# Op-Amp_Stages.net
KiCad netlist of a schematic drawn in Altium Designer
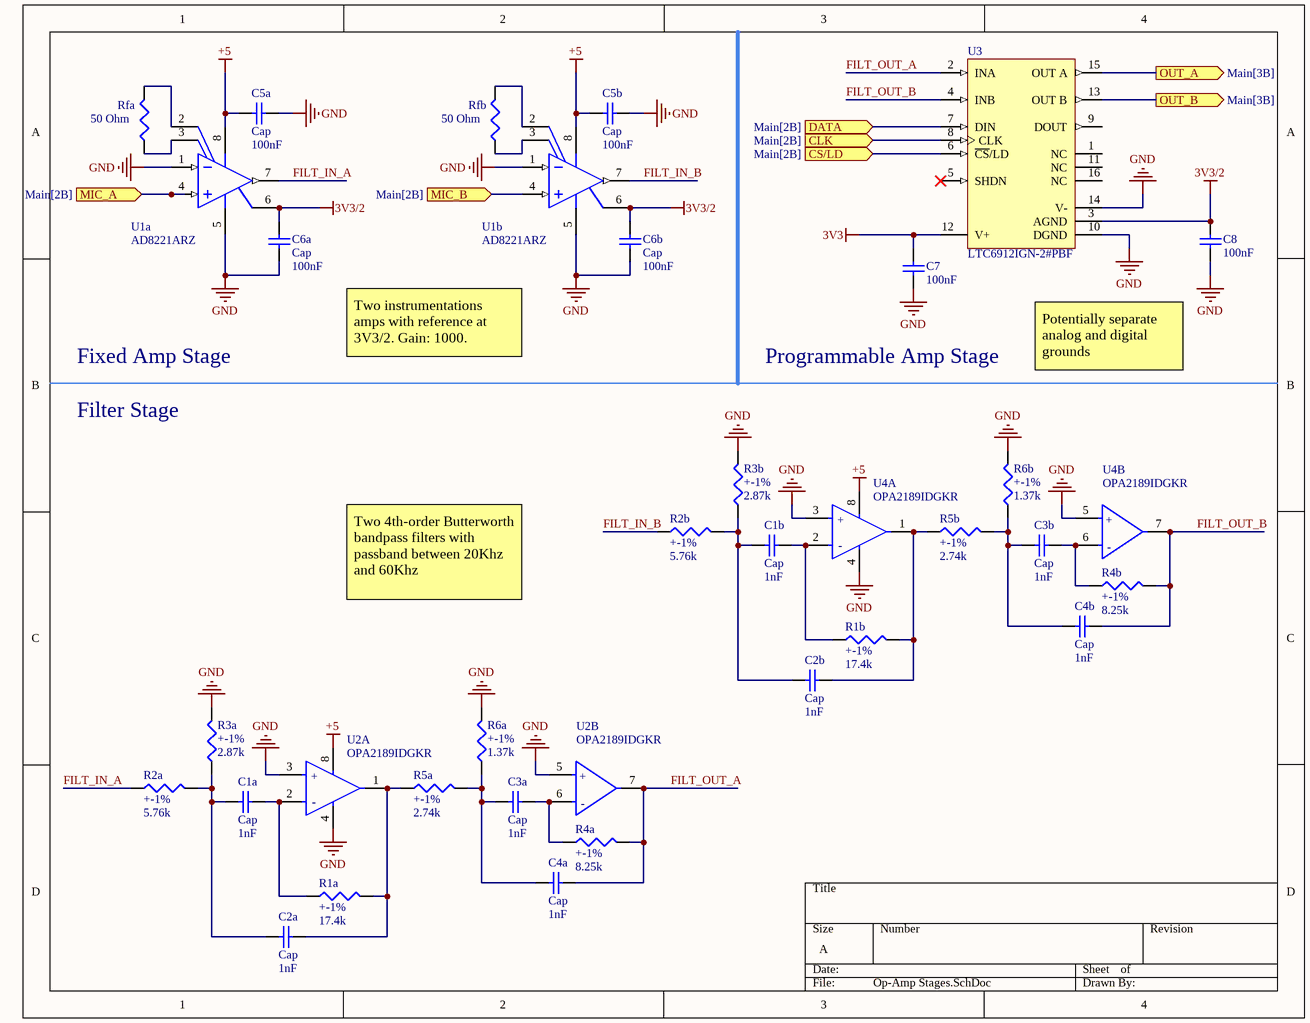
[diagram p0: Op-Amp Stages.SchDoc]

(export (version "E")
  (design (tool "Eeschema 10.0.6"))
  (components
    (comp (ref "C1a")
      (value "Cap")
      (footprint "RAD-0.3")
      (description "Capacitor")
      (fields (field (name "ALTIUM_VALUE") "1nF") (field (name "PUBLISHER") "Altium Limited"))
      (libsource (lib "Miscellaneous Devices") (part "Cap"))
    )
    (comp (ref "C1b")
      (value "Cap")
      (footprint "RAD-0.3")
      (description "Capacitor")
      (fields (field (name "ALTIUM_VALUE") "1nF") (field (name "PUBLISHER") "Altium Limited"))
      (libsource (lib "Miscellaneous Devices") (part "Cap"))
    )
    (comp (ref "C2a")
      (value "Cap")
      (footprint "RAD-0.3")
      (description "Capacitor")
      (fields (field (name "ALTIUM_VALUE") "1nF") (field (name "PUBLISHER") "Altium Limited"))
      (libsource (lib "Miscellaneous Devices") (part "Cap"))
    )
    (comp (ref "C2b")
      (value "Cap")
      (footprint "RAD-0.3")
      (description "Capacitor")
      (fields (field (name "ALTIUM_VALUE") "1nF") (field (name "PUBLISHER") "Altium Limited"))
      (libsource (lib "Miscellaneous Devices") (part "Cap"))
    )
    (comp (ref "C3a")
      (value "Cap")
      (footprint "RAD-0.3")
      (description "Capacitor")
      (fields (field (name "ALTIUM_VALUE") "1nF") (field (name "PUBLISHER") "Altium Limited"))
      (libsource (lib "Miscellaneous Devices") (part "Cap"))
    )
    (comp (ref "C3b")
      (value "Cap")
      (footprint "RAD-0.3")
      (description "Capacitor")
      (fields (field (name "ALTIUM_VALUE") "1nF") (field (name "PUBLISHER") "Altium Limited"))
      (libsource (lib "Miscellaneous Devices") (part "Cap"))
    )
    (comp (ref "C4a")
      (value "Cap")
      (footprint "RAD-0.3")
      (description "Capacitor")
      (fields (field (name "ALTIUM_VALUE") "1nF") (field (name "PUBLISHER") "Altium Limited"))
      (libsource (lib "Miscellaneous Devices") (part "Cap"))
    )
    (comp (ref "C4b")
      (value "Cap")
      (footprint "RAD-0.3")
      (description "Capacitor")
      (fields (field (name "ALTIUM_VALUE") "1nF") (field (name "PUBLISHER") "Altium Limited"))
      (libsource (lib "Miscellaneous Devices") (part "Cap"))
    )
    (comp (ref "C5a")
      (value "Cap")
      (footprint "RAD-0.3")
      (description "Capacitor")
      (fields (field (name "ALTIUM_VALUE") "100nF") (field (name "PUBLISHER") "Altium Limited"))
      (libsource (lib "Miscellaneous Devices") (part "Cap"))
    )
    (comp (ref "C5b")
      (value "Cap")
      (footprint "RAD-0.3")
      (description "Capacitor")
      (fields (field (name "ALTIUM_VALUE") "100nF") (field (name "PUBLISHER") "Altium Limited"))
      (libsource (lib "Miscellaneous Devices") (part "Cap"))
    )
    (comp (ref "C6a")
      (value "Cap")
      (footprint "RAD-0.3")
      (description "Capacitor")
      (fields (field (name "ALTIUM_VALUE") "100nF") (field (name "PUBLISHER") "Altium Limited"))
      (libsource (lib "Miscellaneous Devices") (part "Cap"))
    )
    (comp (ref "C6b")
      (value "Cap")
      (footprint "RAD-0.3")
      (description "Capacitor")
      (fields (field (name "ALTIUM_VALUE") "100nF") (field (name "PUBLISHER") "Altium Limited"))
      (libsource (lib "Miscellaneous Devices") (part "Cap"))
    )
    (comp (ref "C7")
      (value "100nF")
      (footprint "RAD-0.3")
      (description "Capacitor")
      (fields (field (name "PUBLISHER") "Altium Limited"))
      (libsource (lib "Miscellaneous Devices") (part "Cap"))
    )
    (comp (ref "C8")
      (value "100nF")
      (footprint "RAD-0.3")
      (description "Capacitor")
      (fields (field (name "PUBLISHER") "Altium Limited"))
      (libsource (lib "Miscellaneous Devices") (part "Cap"))
    )
    (comp (ref "R1a")
      (value "+-1%")
      (footprint "J1-0603")
      (description "Resistor")
      (fields (field (name "ALTIUM_VALUE") "17.4k") (field (name "PUBLISHER") "Altium Limited"))
      (libsource (lib "Miscellaneous Devices") (part "Res3"))
    )
    (comp (ref "R1b")
      (value "+-1%")
      (footprint "J1-0603")
      (description "Resistor")
      (fields (field (name "ALTIUM_VALUE") "17.4k") (field (name "PUBLISHER") "Altium Limited"))
      (libsource (lib "Miscellaneous Devices") (part "Res3"))
    )
    (comp (ref "R2a")
      (value "+-1%")
      (footprint "J1-0603")
      (description "Resistor")
      (fields (field (name "ALTIUM_VALUE") "5.76k") (field (name "PUBLISHER") "Altium Limited"))
      (libsource (lib "Miscellaneous Devices") (part "Res3"))
    )
    (comp (ref "R2b")
      (value "+-1%")
      (footprint "J1-0603")
      (description "Resistor")
      (fields (field (name "ALTIUM_VALUE") "5.76k") (field (name "PUBLISHER") "Altium Limited"))
      (libsource (lib "Miscellaneous Devices") (part "Res3"))
    )
    (comp (ref "R3a")
      (value "+-1%")
      (footprint "J1-0603")
      (description "Resistor")
      (fields (field (name "ALTIUM_VALUE") "2.87k") (field (name "PUBLISHER") "Altium Limited"))
      (libsource (lib "Miscellaneous Devices") (part "Res3"))
    )
    (comp (ref "R3b")
      (value "+-1%")
      (footprint "J1-0603")
      (description "Resistor")
      (fields (field (name "ALTIUM_VALUE") "2.87k") (field (name "PUBLISHER") "Altium Limited"))
      (libsource (lib "Miscellaneous Devices") (part "Res3"))
    )
    (comp (ref "R4a")
      (value "+-1%")
      (footprint "J1-0603")
      (description "Resistor")
      (fields (field (name "ALTIUM_VALUE") "8.25k") (field (name "PUBLISHER") "Altium Limited"))
      (libsource (lib "Miscellaneous Devices") (part "Res3"))
    )
    (comp (ref "R4b")
      (value "+-1%")
      (footprint "J1-0603")
      (description "Resistor")
      (fields (field (name "ALTIUM_VALUE") "8.25k") (field (name "PUBLISHER") "Altium Limited"))
      (libsource (lib "Miscellaneous Devices") (part "Res3"))
    )
    (comp (ref "R5a")
      (value "+-1%")
      (footprint "J1-0603")
      (description "Resistor")
      (fields (field (name "ALTIUM_VALUE") "2.74k") (field (name "PUBLISHER") "Altium Limited"))
      (libsource (lib "Miscellaneous Devices") (part "Res3"))
    )
    (comp (ref "R5b")
      (value "+-1%")
      (footprint "J1-0603")
      (description "Resistor")
      (fields (field (name "ALTIUM_VALUE") "2.74k") (field (name "PUBLISHER") "Altium Limited"))
      (libsource (lib "Miscellaneous Devices") (part "Res3"))
    )
    (comp (ref "R6a")
      (value "+-1%")
      (footprint "J1-0603")
      (description "Resistor")
      (fields (field (name "ALTIUM_VALUE") "1.37k") (field (name "PUBLISHER") "Altium Limited"))
      (libsource (lib "Miscellaneous Devices") (part "Res3"))
    )
    (comp (ref "R6b")
      (value "+-1%")
      (footprint "J1-0603")
      (description "Resistor")
      (fields (field (name "ALTIUM_VALUE") "1.37k") (field (name "PUBLISHER") "Altium Limited"))
      (libsource (lib "Miscellaneous Devices") (part "Res3"))
    )
    (comp (ref "Rfa")
      (value "50 Ohm")
      (footprint "J1-0603")
      (description "Resistor")
      (fields (field (name "PUBLISHER") "Altium Limited"))
      (libsource (lib "Miscellaneous Devices") (part "Res3"))
    )
    (comp (ref "Rfb")
      (value "50 Ohm")
      (footprint "J1-0603")
      (description "Resistor")
      (fields (field (name "PUBLISHER") "Altium Limited"))
      (libsource (lib "Miscellaneous Devices") (part "Res3"))
    )
    (comp (ref "U1a")
      (value "AD8221ARZ")
      (footprint "ADI-R-8_M")
      (description "Precision Instrumentation Amplifier, 2 V/us, -40 to 125 degC, 8-Pin SOIC (R-8), RoHS, Tube")
      (fields (field (name "MANUFACTURER") "Analog Devices"))
      (libsource (lib "Altium Content Vault") (part "ADI-AD8221-8"))
    )
    (comp (ref "U1b")
      (value "AD8221ARZ")
      (footprint "ADI-R-8_M")
      (description "Precision Instrumentation Amplifier, 2 V/us, -40 to 125 degC, 8-Pin SOIC (R-8), RoHS, Tube")
      (fields (field (name "MANUFACTURER") "Analog Devices"))
      (libsource (lib "Altium Content Vault") (part "ADI-AD8221-8"))
    )
    (comp (ref "U2")
      (value "OPA2189IDGKR")
      (footprint "FP-DGK0008A-IPC_B")
      (description "DUAL, 14MHZ, MUX-FRIENDLY, LOW-N")
      (libsource (lib "Altium Content Vault") (part "499df5fc91ff7ad023bcaf249d8becd"))
    )
    (comp (ref "U3")
      (value "LTC6912IGN-2#PBF")
      (footprint "LT-GN-16_L")
      (fields
        (field (name "MANUFACTURER") "Linear Technology")
        (field (name "LINEAR TECHNOLOGY PART NUMBER") "LTC6912-2")
      )
      (libsource (lib "Altium Content Vault") (part "LT-LTC6912-2-GN-16"))
    )
    (comp (ref "U4")
      (value "OPA2189IDGKR")
      (footprint "FP-DGK0008A-IPC_B")
      (description "DUAL, 14MHZ, MUX-FRIENDLY, LOW-N")
      (libsource (lib "Altium Content Vault") (part "499df5fc91ff7ad023bcaf249d8becd"))
    )
  )
  (nets
    (net (code "1") (name "+5") (class "Default")
      (node (ref "C5a") (pin "1") (pinfunction "1_1") (pintype "passive"))
      (node (ref "C5b") (pin "1") (pinfunction "1_1") (pintype "passive"))
      (node (ref "U1a") (pin "8") (pinfunction "VS+_8") (pintype "power_in"))
      (node (ref "U1b") (pin "8") (pinfunction "VS+_8") (pintype "power_in"))
      (node (ref "U2") (pin "8") (pinfunction "V+_8") (pintype "power_in"))
      (node (ref "U4") (pin "8") (pinfunction "V+_8") (pintype "power_in"))
    )
    (net (code "2") (name "/CLK") (class "Default")
      (node (ref "U3") (pin "8") (pinfunction "CLK_8") (pintype "input"))
    )
    (net (code "3") (name "/CS{slash}LD") (class "Default")
      (node (ref "U3") (pin "6") (pinfunction "~{CS}/LD_6") (pintype "input"))
    )
    (net (code "4") (name "/DATA") (class "Default")
      (node (ref "U3") (pin "7") (pinfunction "DIN_7") (pintype "input"))
    )
    (net (code "5") (name "/FILT_IN_A") (class "Default")
      (node (ref "R2a") (pin "1") (pinfunction "1_1") (pintype "passive"))
      (node (ref "U1a") (pin "7") (pinfunction "VOUT_7") (pintype "output"))
    )
    (net (code "6") (name "/FILT_IN_B") (class "Default")
      (node (ref "R2b") (pin "1") (pinfunction "1_1") (pintype "passive"))
      (node (ref "U1b") (pin "7") (pinfunction "VOUT_7") (pintype "output"))
    )
    (net (code "7") (name "/FILT_OUT_A") (class "Default")
      (node (ref "C4a") (pin "2") (pinfunction "2_2") (pintype "passive"))
      (node (ref "R4a") (pin "2") (pinfunction "2_2") (pintype "passive"))
      (node (ref "U2") (pin "7") (pinfunction "OUT_B_7") (pintype "passive"))
      (node (ref "U3") (pin "2") (pinfunction "INA_2") (pintype "input"))
    )
    (net (code "8") (name "/FILT_OUT_B") (class "Default")
      (node (ref "C4b") (pin "2") (pinfunction "2_2") (pintype "passive"))
      (node (ref "R4b") (pin "2") (pinfunction "2_2") (pintype "passive"))
      (node (ref "U3") (pin "4") (pinfunction "INB_4") (pintype "input"))
      (node (ref "U4") (pin "7") (pinfunction "OUT_B_7") (pintype "passive"))
    )
    (net (code "9") (name "/MIC_A") (class "Default")
      (node (ref "U1a") (pin "4") (pinfunction "IN+_4") (pintype "input"))
    )
    (net (code "10") (name "/MIC_B") (class "Default")
      (node (ref "U1b") (pin "4") (pinfunction "IN+_4") (pintype "input"))
    )
    (net (code "11") (name "/OUT_A") (class "Default")
      (node (ref "U3") (pin "15") (pinfunction "OUT_A_15") (pintype "output"))
    )
    (net (code "12") (name "/OUT_B") (class "Default")
      (node (ref "U3") (pin "13") (pinfunction "OUT_B_13") (pintype "output"))
    )
    (net (code "13") (name "3V3") (class "Default")
      (node (ref "C7") (pin "2") (pinfunction "2_2") (pintype "passive"))
      (node (ref "U3") (pin "12") (pinfunction "V+_12") (pintype "power_in"))
    )
    (net (code "14") (name "3V3{slash}2") (class "Default")
      (node (ref "C6a") (pin "2") (pinfunction "2_2") (pintype "passive"))
      (node (ref "C6b") (pin "2") (pinfunction "2_2") (pintype "passive"))
      (node (ref "C8") (pin "2") (pinfunction "2_2") (pintype "passive"))
      (node (ref "U1a") (pin "6") (pinfunction "REF_6") (pintype "passive"))
      (node (ref "U1b") (pin "6") (pinfunction "REF_6") (pintype "passive"))
      (node (ref "U3") (pin "3") (pinfunction "AGND_3") (pintype "power_in"))
    )
    (net (code "15") (name "GND") (class "Default")
      (node (ref "C5a") (pin "2") (pinfunction "2_2") (pintype "passive"))
      (node (ref "C5b") (pin "2") (pinfunction "2_2") (pintype "passive"))
      (node (ref "C6a") (pin "1") (pinfunction "1_1") (pintype "passive"))
      (node (ref "C6b") (pin "1") (pinfunction "1_1") (pintype "passive"))
      (node (ref "C7") (pin "1") (pinfunction "1_1") (pintype "passive"))
      (node (ref "C8") (pin "1") (pinfunction "1_1") (pintype "passive"))
      (node (ref "R3a") (pin "2") (pinfunction "2_2") (pintype "passive"))
      (node (ref "R3b") (pin "2") (pinfunction "2_2") (pintype "passive"))
      (node (ref "R6a") (pin "2") (pinfunction "2_2") (pintype "passive"))
      (node (ref "R6b") (pin "2") (pinfunction "2_2") (pintype "passive"))
      (node (ref "U1a") (pin "1") (pinfunction "IN-_1") (pintype "input"))
      (node (ref "U1a") (pin "5") (pinfunction "VS-_5") (pintype "power_in"))
      (node (ref "U1b") (pin "1") (pinfunction "IN-_1") (pintype "input"))
      (node (ref "U1b") (pin "5") (pinfunction "VS-_5") (pintype "power_in"))
      (node (ref "U2") (pin "3") (pinfunction "+IN_A_3") (pintype "tri_state"))
      (node (ref "U2") (pin "4") (pinfunction "V-_4") (pintype "power_in"))
      (node (ref "U2") (pin "5") (pinfunction "+IN_B_5") (pintype "tri_state"))
      (node (ref "U3") (pin "10") (pinfunction "DGND_10") (pintype "power_in"))
      (node (ref "U3") (pin "14") (pinfunction "V-_14") (pintype "power_in"))
      (node (ref "U4") (pin "3") (pinfunction "+IN_A_3") (pintype "tri_state"))
      (node (ref "U4") (pin "4") (pinfunction "V-_4") (pintype "power_in"))
      (node (ref "U4") (pin "5") (pinfunction "+IN_B_5") (pintype "tri_state"))
    )
    (net (code "16") (name "Net-(C1a-Pad1)") (class "Default")
      (node (ref "C1a") (pin "1") (pinfunction "1_1") (pintype "passive"))
      (node (ref "C2a") (pin "1") (pinfunction "1_1") (pintype "passive"))
      (node (ref "R2a") (pin "2") (pinfunction "2_2") (pintype "passive"))
      (node (ref "R3a") (pin "1") (pinfunction "1_1") (pintype "passive"))
    )
    (net (code "17") (name "Net-(C1b-Pad1)") (class "Default")
      (node (ref "C1b") (pin "1") (pinfunction "1_1") (pintype "passive"))
      (node (ref "C2b") (pin "1") (pinfunction "1_1") (pintype "passive"))
      (node (ref "R2b") (pin "2") (pinfunction "2_2") (pintype "passive"))
      (node (ref "R3b") (pin "1") (pinfunction "1_1") (pintype "passive"))
    )
    (net (code "18") (name "Net-(C3a-Pad1)") (class "Default")
      (node (ref "C3a") (pin "1") (pinfunction "1_1") (pintype "passive"))
      (node (ref "C4a") (pin "1") (pinfunction "1_1") (pintype "passive"))
      (node (ref "R5a") (pin "2") (pinfunction "2_2") (pintype "passive"))
      (node (ref "R6a") (pin "1") (pinfunction "1_1") (pintype "passive"))
    )
    (net (code "19") (name "Net-(C3b-Pad1)") (class "Default")
      (node (ref "C3b") (pin "1") (pinfunction "1_1") (pintype "passive"))
      (node (ref "C4b") (pin "1") (pinfunction "1_1") (pintype "passive"))
      (node (ref "R5b") (pin "2") (pinfunction "2_2") (pintype "passive"))
      (node (ref "R6b") (pin "1") (pinfunction "1_1") (pintype "passive"))
    )
    (net (code "20") (name "Net-(Rfa-Pad1)") (class "Default")
      (node (ref "Rfa") (pin "1") (pinfunction "1_1") (pintype "passive"))
      (node (ref "U1a") (pin "3") (pinfunction "RG_3") (pintype "passive"))
    )
    (net (code "21") (name "Net-(Rfa-Pad2)") (class "Default")
      (node (ref "Rfa") (pin "2") (pinfunction "2_2") (pintype "passive"))
      (node (ref "U1a") (pin "2") (pinfunction "RG_2") (pintype "passive"))
    )
    (net (code "22") (name "Net-(Rfb-Pad1)") (class "Default")
      (node (ref "Rfb") (pin "1") (pinfunction "1_1") (pintype "passive"))
      (node (ref "U1b") (pin "3") (pinfunction "RG_3") (pintype "passive"))
    )
    (net (code "23") (name "Net-(Rfb-Pad2)") (class "Default")
      (node (ref "Rfb") (pin "2") (pinfunction "2_2") (pintype "passive"))
      (node (ref "U1b") (pin "2") (pinfunction "RG_2") (pintype "passive"))
    )
    (net (code "24") (name "Net-(U2A--IN_A)") (class "Default")
      (node (ref "C1a") (pin "2") (pinfunction "2_2") (pintype "passive"))
      (node (ref "R1a") (pin "1") (pinfunction "1_1") (pintype "passive"))
      (node (ref "U2") (pin "2") (pinfunction "-IN_A_2") (pintype "tri_state"))
    )
    (net (code "25") (name "Net-(U2A-OUT_A)") (class "Default")
      (node (ref "C2a") (pin "2") (pinfunction "2_2") (pintype "passive"))
      (node (ref "R1a") (pin "2") (pinfunction "2_2") (pintype "passive"))
      (node (ref "R5a") (pin "1") (pinfunction "1_1") (pintype "passive"))
      (node (ref "U2") (pin "1") (pinfunction "OUT_A_1") (pintype "passive"))
    )
    (net (code "26") (name "Net-(U2B--IN_B)") (class "Default")
      (node (ref "C3a") (pin "2") (pinfunction "2_2") (pintype "passive"))
      (node (ref "R4a") (pin "1") (pinfunction "1_1") (pintype "passive"))
      (node (ref "U2") (pin "6") (pinfunction "-IN_B_6") (pintype "tri_state"))
    )
    (net (code "27") (name "Net-(U4A--IN_A)") (class "Default")
      (node (ref "C1b") (pin "2") (pinfunction "2_2") (pintype "passive"))
      (node (ref "R1b") (pin "1") (pinfunction "1_1") (pintype "passive"))
      (node (ref "U4") (pin "2") (pinfunction "-IN_A_2") (pintype "tri_state"))
    )
    (net (code "28") (name "Net-(U4A-OUT_A)") (class "Default")
      (node (ref "C2b") (pin "2") (pinfunction "2_2") (pintype "passive"))
      (node (ref "R1b") (pin "2") (pinfunction "2_2") (pintype "passive"))
      (node (ref "R5b") (pin "1") (pinfunction "1_1") (pintype "passive"))
      (node (ref "U4") (pin "1") (pinfunction "OUT_A_1") (pintype "passive"))
    )
    (net (code "29") (name "Net-(U4B--IN_B)") (class "Default")
      (node (ref "C3b") (pin "2") (pinfunction "2_2") (pintype "passive"))
      (node (ref "R4b") (pin "1") (pinfunction "1_1") (pintype "passive"))
      (node (ref "U4") (pin "6") (pinfunction "-IN_B_6") (pintype "tri_state"))
    )
    (net (code "30") (name "unconnected-(U3-DOUT-Pad9)") (class "Default")
      (node (ref "U3") (pin "9") (pinfunction "DOUT_9") (pintype "output"))
    )
    (net (code "31") (name "unconnected-(U3-NC-Pad1)") (class "Default")
      (node (ref "U3") (pin "1") (pinfunction "NC_1") (pintype "passive"))
    )
    (net (code "32") (name "unconnected-(U3-NC-Pad11)") (class "Default")
      (node (ref "U3") (pin "11") (pinfunction "NC_11") (pintype "passive"))
    )
    (net (code "33") (name "unconnected-(U3-NC-Pad16)") (class "Default")
      (node (ref "U3") (pin "16") (pinfunction "NC_16") (pintype "passive"))
    )
    (net (code "34") (name "unconnected-(U3-SHDN-Pad5)") (class "Default")
      (node (ref "U3") (pin "5") (pinfunction "SHDN_5") (pintype "input+no_connect"))
    )
  )
)
